# TPS6122x.net
KiCad netlist of a schematic drawn in EAGLE
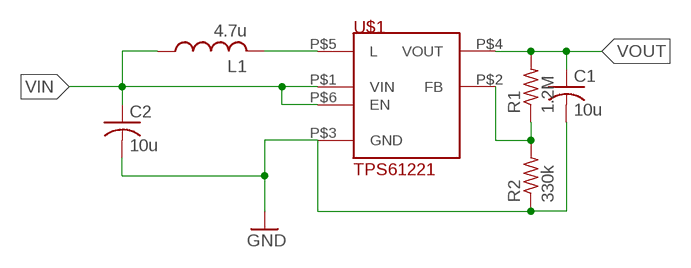
[diagram p0: schematic, sheet 1]

(export (version "E")
  (design (tool "Eeschema 10.0.6"))
  (components
    (comp (ref "C1")
      (value "10u")
      (footprint "eagle-import:C3216")
      (libsource (lib "eagle-import") (part "C-USC3216"))
    )
    (comp (ref "C2")
      (value "10u")
      (footprint "eagle-import:C3216")
      (libsource (lib "eagle-import") (part "C-USC3216"))
    )
    (comp (ref "L1")
      (value "4.7u")
      (footprint "eagle-import:L1210")
      (libsource (lib "eagle-import") (part "L-USL1210"))
    )
    (comp (ref "R1")
      (value "1.2M")
      (footprint "eagle-import:R0603")
      (libsource (lib "eagle-import") (part "R-US_R0603"))
    )
    (comp (ref "R2")
      (value "330k")
      (footprint "eagle-import:R0603")
      (libsource (lib "eagle-import") (part "R-US_R0603"))
    )
    (comp (ref "U$1")
      (value "TPS61221")
      (footprint "eagle-import:TPS61221")
      (libsource (lib "eagle-import") (part "TPS61221"))
    )
  )
  (nets
    (net (code "1") (name "GND") (class "Default")
      (node (ref "C1") (pin "2") (pinfunction "2_2") (pintype "passive"))
      (node (ref "C2") (pin "2") (pinfunction "2_2") (pintype "passive"))
      (node (ref "R2") (pin "1") (pinfunction "1_1") (pintype "passive"))
      (node (ref "U$1") (pin "P$3") (pinfunction "GND_P$3") (pintype "bidirectional"))
    )
    (net (code "2") (name "Net-(U$1-FB)") (class "Default")
      (node (ref "R1") (pin "1") (pinfunction "1_1") (pintype "passive"))
      (node (ref "R2") (pin "2") (pinfunction "2_2") (pintype "passive"))
      (node (ref "U$1") (pin "P$2") (pinfunction "FB_P$2") (pintype "bidirectional"))
    )
    (net (code "3") (name "Net-(U$1-L)") (class "Default")
      (node (ref "L1") (pin "2") (pinfunction "2_2") (pintype "passive"))
      (node (ref "U$1") (pin "P$5") (pinfunction "L_P$5") (pintype "bidirectional"))
    )
    (net (code "4") (name "VIN") (class "Default")
      (node (ref "C2") (pin "1") (pinfunction "1_1") (pintype "passive"))
      (node (ref "L1") (pin "1") (pinfunction "1_1") (pintype "passive"))
      (node (ref "U$1") (pin "P$1") (pinfunction "VIN_P$1") (pintype "bidirectional"))
      (node (ref "U$1") (pin "P$6") (pinfunction "EN_P$6") (pintype "bidirectional"))
    )
    (net (code "5") (name "VOUT") (class "Default")
      (node (ref "C1") (pin "1") (pinfunction "1_1") (pintype "passive"))
      (node (ref "R1") (pin "2") (pinfunction "2_2") (pintype "passive"))
      (node (ref "U$1") (pin "P$4") (pinfunction "VOUT_P$4") (pintype "bidirectional"))
    )
  )
)
